# controllo_motori_-_encoder_r2.net
KiCad netlist of a schematic drawn in EAGLE
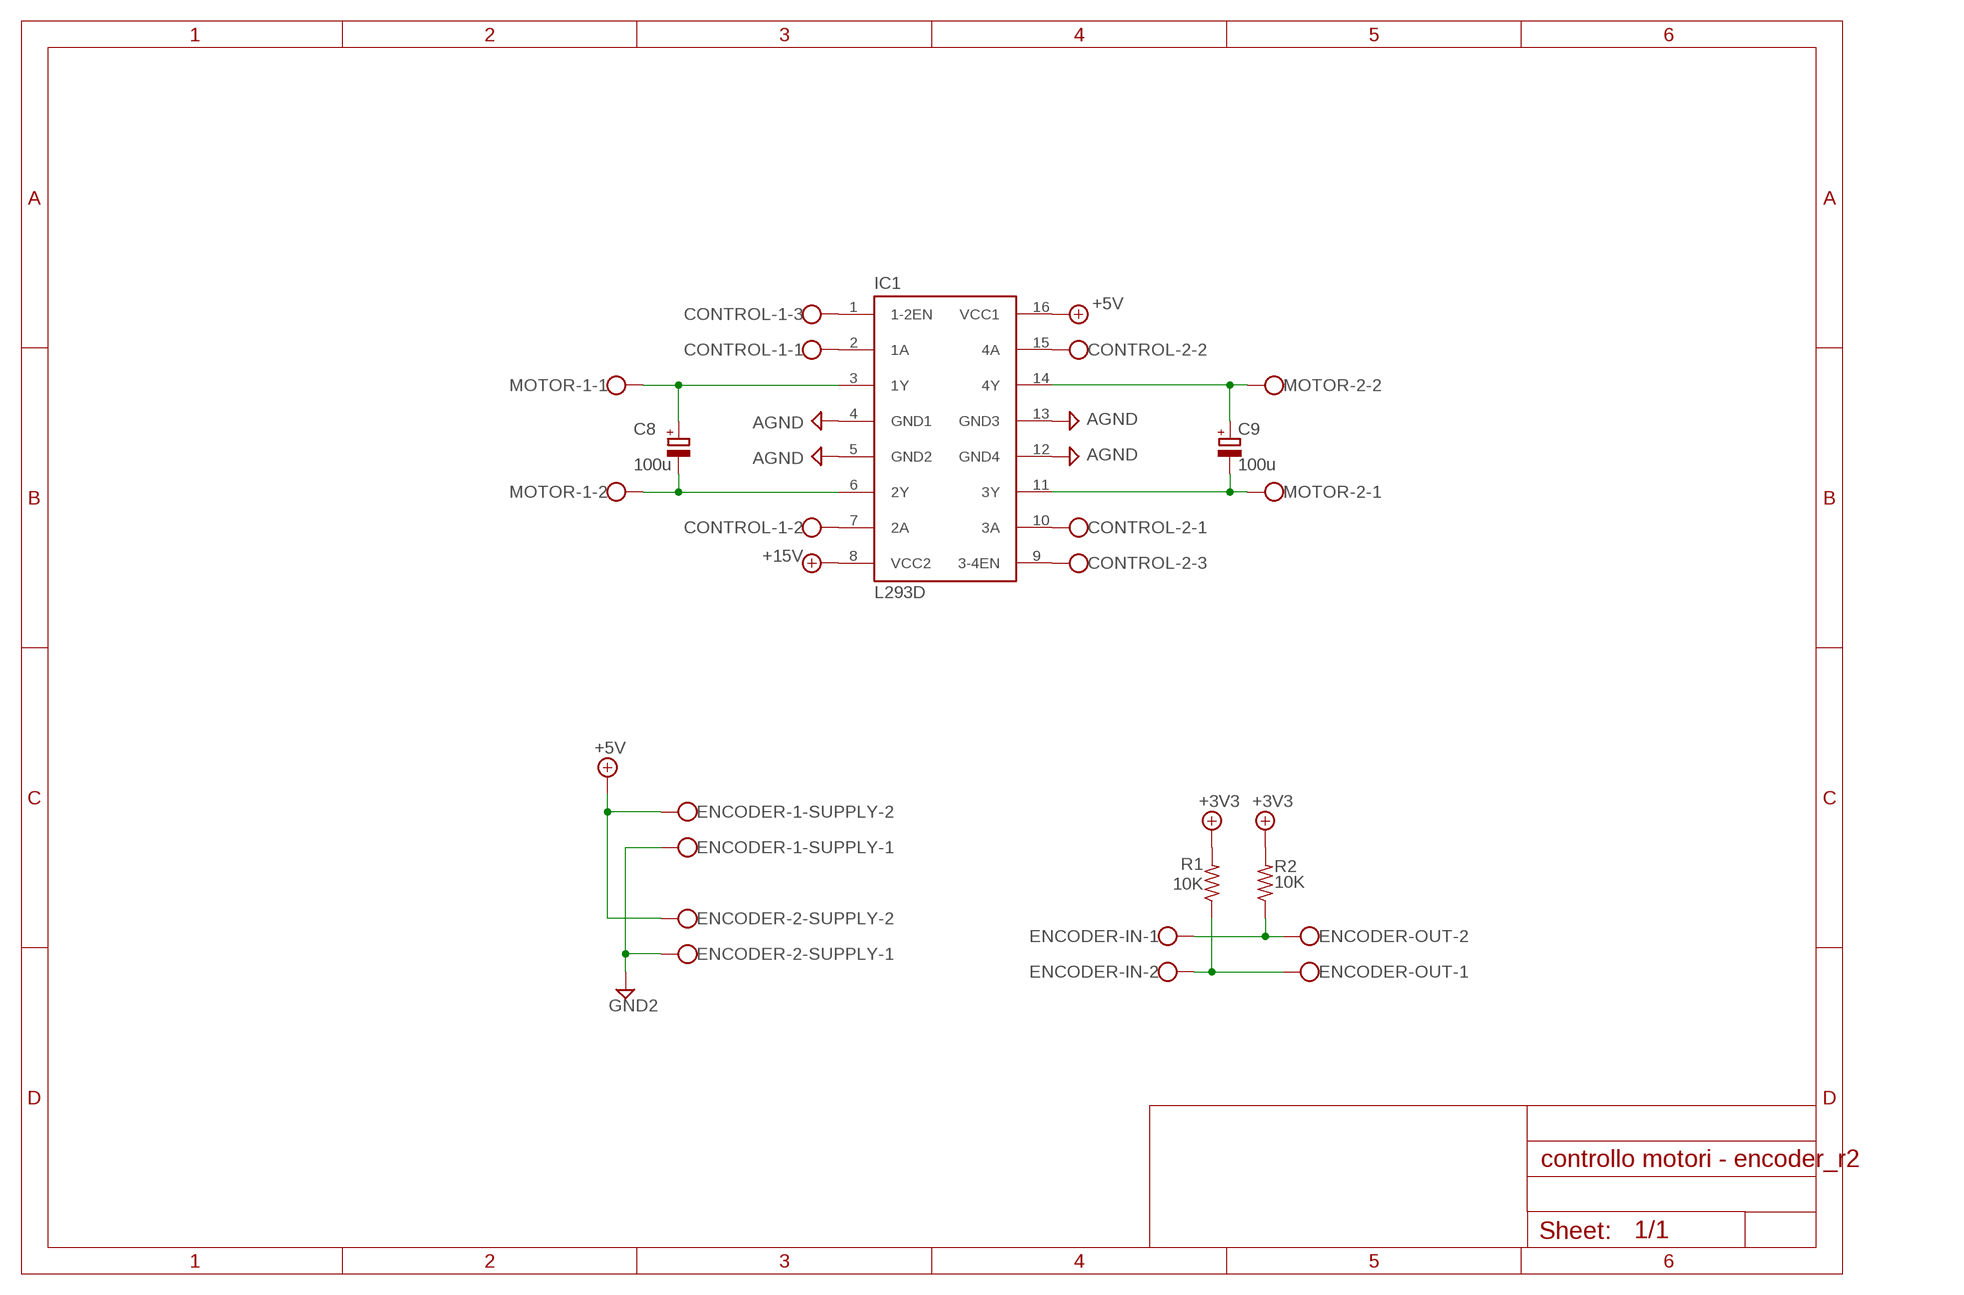
[diagram p0: schematic, sheet 1]

(export (version "E")
  (design (tool "Eeschema 10.0.6"))
  (components
    (comp (ref "C8")
      (value "100u")
      (footprint "eagle-import:B45181B")
      (libsource (lib "eagle-import") (part "CPOL-EUB45181B"))
    )
    (comp (ref "C9")
      (value "100u")
      (footprint "eagle-import:B45181B")
      (libsource (lib "eagle-import") (part "CPOL-EUB45181B"))
    )
    (comp (ref "CONTROL-1")
      (value "W237-103")
      (footprint "eagle-import:W237-103")
      (fields (field (name "MPN") "237-103"))
      (libsource (lib "eagle-import") (part "W237-103"))
    )
    (comp (ref "CONTROL-2")
      (value "W237-103")
      (footprint "eagle-import:W237-103")
      (fields (field (name "MPN") "237-103"))
      (libsource (lib "eagle-import") (part "W237-103"))
    )
    (comp (ref "ENCODER-1-SUPPLY")
      (value "W237-102")
      (footprint "eagle-import:W237-102")
      (fields (field (name "MPN") "237-102"))
      (libsource (lib "eagle-import") (part "W237-102"))
    )
    (comp (ref "ENCODER-2-SUPPLY")
      (value "W237-102")
      (footprint "eagle-import:W237-102")
      (fields (field (name "MPN") "237-102"))
      (libsource (lib "eagle-import") (part "W237-102"))
    )
    (comp (ref "ENCODER-IN")
      (value "W237-102")
      (footprint "eagle-import:W237-102")
      (fields (field (name "MPN") "237-102"))
      (libsource (lib "eagle-import") (part "W237-102"))
    )
    (comp (ref "ENCODER-OUT")
      (value "W237-102")
      (footprint "eagle-import:W237-102")
      (fields (field (name "MPN") "237-102"))
      (libsource (lib "eagle-import") (part "W237-102"))
    )
    (comp (ref "IC1")
      (value "L293D")
      (footprint "eagle-import:DIL16")
      (libsource (lib "eagle-import") (part "L293D"))
    )
    (comp (ref "MOTOR-1")
      (value "W237-102")
      (footprint "eagle-import:W237-102")
      (fields (field (name "MPN") "237-102"))
      (libsource (lib "eagle-import") (part "W237-102"))
    )
    (comp (ref "MOTOR-2")
      (value "W237-102")
      (footprint "eagle-import:W237-102")
      (fields (field (name "MPN") "237-102"))
      (libsource (lib "eagle-import") (part "W237-102"))
    )
    (comp (ref "R1")
      (value "10K")
      (footprint "eagle-import:0204_7")
      (libsource (lib "eagle-import") (part "R-US_0204/7"))
    )
    (comp (ref "R2")
      (value "10K")
      (footprint "eagle-import:0204_7")
      (libsource (lib "eagle-import") (part "R-US_0204/7"))
    )
  )
  (nets
    (net (code "1") (name "+3V3") (class "Default")
      (node (ref "R1") (pin "2") (pinfunction "2_2") (pintype "passive"))
      (node (ref "R2") (pin "2") (pinfunction "2_2") (pintype "passive"))
    )
    (net (code "2") (name "+5V") (class "Default")
      (node (ref "ENCODER-1-SUPPLY") (pin "2") (pinfunction "KL_2") (pintype "passive"))
      (node (ref "ENCODER-2-SUPPLY") (pin "2") (pinfunction "KL_2") (pintype "passive"))
      (node (ref "IC1") (pin "16") (pinfunction "VCC1_16") (pintype "power_in"))
    )
    (net (code "3") (name "+15V") (class "Default")
      (node (ref "IC1") (pin "8") (pinfunction "VCC2_8") (pintype "power_in"))
    )
    (net (code "4") (name "AGND") (class "Default")
      (node (ref "IC1") (pin "12") (pinfunction "GND4_12") (pintype "power_in"))
      (node (ref "IC1") (pin "13") (pinfunction "GND3_13") (pintype "power_in"))
      (node (ref "IC1") (pin "4") (pinfunction "GND1_4") (pintype "power_in"))
      (node (ref "IC1") (pin "5") (pinfunction "GND2_5") (pintype "power_in"))
    )
    (net (code "5") (name "GND2") (class "Default")
      (node (ref "ENCODER-1-SUPPLY") (pin "1") (pinfunction "KL_1") (pintype "passive"))
      (node (ref "ENCODER-2-SUPPLY") (pin "1") (pinfunction "KL_1") (pintype "passive"))
    )
    (net (code "6") (name "Net-(CONTROL-1A-KL)") (class "Default")
      (node (ref "CONTROL-1") (pin "1") (pinfunction "KL_1") (pintype "passive"))
      (node (ref "IC1") (pin "2") (pinfunction "1A_2") (pintype "input"))
    )
    (net (code "7") (name "Net-(CONTROL-1B-KL)") (class "Default")
      (node (ref "CONTROL-1") (pin "2") (pinfunction "KL_2") (pintype "passive"))
      (node (ref "IC1") (pin "7") (pinfunction "2A_7") (pintype "input"))
    )
    (net (code "8") (name "Net-(CONTROL-1C-KL)") (class "Default")
      (node (ref "CONTROL-1") (pin "3") (pinfunction "KL_3") (pintype "passive"))
      (node (ref "IC1") (pin "1") (pinfunction "1-2EN_1") (pintype "input"))
    )
    (net (code "9") (name "Net-(CONTROL-2A-KL)") (class "Default")
      (node (ref "CONTROL-2") (pin "1") (pinfunction "KL_1") (pintype "passive"))
      (node (ref "IC1") (pin "10") (pinfunction "3A_10") (pintype "input"))
    )
    (net (code "10") (name "Net-(CONTROL-2B-KL)") (class "Default")
      (node (ref "CONTROL-2") (pin "2") (pinfunction "KL_2") (pintype "passive"))
      (node (ref "IC1") (pin "15") (pinfunction "4A_15") (pintype "input"))
    )
    (net (code "11") (name "Net-(CONTROL-2C-KL)") (class "Default")
      (node (ref "CONTROL-2") (pin "3") (pinfunction "KL_3") (pintype "passive"))
      (node (ref "IC1") (pin "9") (pinfunction "3-4EN_9") (pintype "input"))
    )
    (net (code "12") (name "Net-(ENCODER-INA-KL)") (class "Default")
      (node (ref "ENCODER-IN") (pin "1") (pinfunction "KL_1") (pintype "passive"))
      (node (ref "ENCODER-OUT") (pin "2") (pinfunction "KL_2") (pintype "passive"))
      (node (ref "R2") (pin "1") (pinfunction "1_1") (pintype "passive"))
    )
    (net (code "13") (name "Net-(ENCODER-INB-KL)") (class "Default")
      (node (ref "ENCODER-IN") (pin "2") (pinfunction "KL_2") (pintype "passive"))
      (node (ref "ENCODER-OUT") (pin "1") (pinfunction "KL_1") (pintype "passive"))
      (node (ref "R1") (pin "1") (pinfunction "1_1") (pintype "passive"))
    )
    (net (code "14") (name "Net-(IC1-1Y)") (class "Default")
      (node (ref "C8") (pin "+") (pinfunction "+_+") (pintype "passive"))
      (node (ref "IC1") (pin "3") (pinfunction "1Y_3") (pintype "output"))
      (node (ref "MOTOR-1") (pin "1") (pinfunction "KL_1") (pintype "passive"))
    )
    (net (code "15") (name "Net-(IC1-2Y)") (class "Default")
      (node (ref "C8") (pin "-") (pinfunction "-_-") (pintype "passive"))
      (node (ref "IC1") (pin "6") (pinfunction "2Y_6") (pintype "output"))
      (node (ref "MOTOR-1") (pin "2") (pinfunction "KL_2") (pintype "passive"))
    )
    (net (code "16") (name "Net-(IC1-3Y)") (class "Default")
      (node (ref "C9") (pin "-") (pinfunction "-_-") (pintype "passive"))
      (node (ref "IC1") (pin "11") (pinfunction "3Y_11") (pintype "output"))
      (node (ref "MOTOR-2") (pin "1") (pinfunction "KL_1") (pintype "passive"))
    )
    (net (code "17") (name "Net-(IC1-4Y)") (class "Default")
      (node (ref "C9") (pin "+") (pinfunction "+_+") (pintype "passive"))
      (node (ref "IC1") (pin "14") (pinfunction "4Y_14") (pintype "output"))
      (node (ref "MOTOR-2") (pin "2") (pinfunction "KL_2") (pintype "passive"))
    )
  )
)
